# UNDP_Shield_LoRa.net
KiCad netlist of a schematic drawn in EAGLE
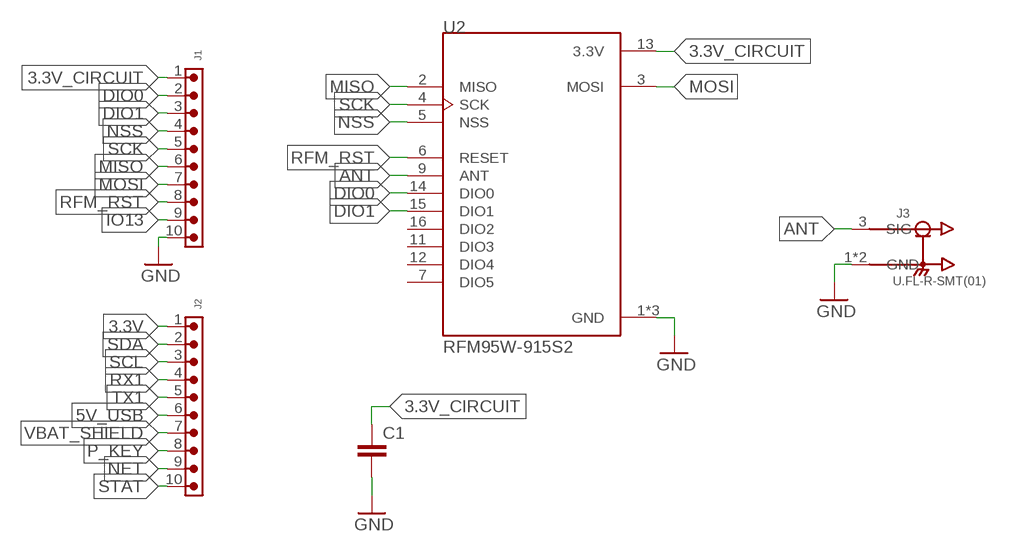
[diagram p0: schematic, sheet 1]

(export (version "E")
  (design (tool "Eeschema 10.0.6"))
  (components
    (comp (ref "C1")
      (value "C-EUC0603")
      (footprint "eagle-import:C0603")
      (libsource (lib "eagle-import") (part "C-EUC0603"))
    )
    (comp (ref "J1")
      (value "6200XX11121_62001011121")
      (footprint "eagle-import:62001011121")
      (libsource (lib "eagle-import") (part "6200XX11121_62001011121"))
    )
    (comp (ref "J2")
      (value "6200XX11121_62001011121")
      (footprint "eagle-import:62001011121")
      (libsource (lib "eagle-import") (part "6200XX11121_62001011121"))
    )
    (comp (ref "J3")
      (value "U.FL-R-SMT(01)")
      (footprint "eagle-import:HRS_U.FL-R-SMT(01)")
      (fields (field (name "MF") "Hirose"))
      (libsource (lib "eagle-import") (part "U.FL-R-SMT(01)"))
    )
    (comp (ref "U2")
      (value "RFM95W-915S2")
      (footprint "eagle-import:XCVR_RFM95W-915S2")
      (fields (field (name "MF") "RF Solutions"))
      (libsource (lib "eagle-import") (part "RFM95W-915S2"))
    )
  )
  (nets
    (net (code "1") (name "3.3V") (class "Default")
      (node (ref "J2") (pin "1") (pinfunction "1_1") (pintype "passive"))
    )
    (net (code "2") (name "3.3V_CIRCUIT") (class "Default")
      (node (ref "C1") (pin "1") (pinfunction "1_1") (pintype "passive"))
      (node (ref "J1") (pin "1") (pinfunction "1_1") (pintype "passive"))
      (node (ref "U2") (pin "13") (pinfunction "3.3V_13") (pintype "power_in"))
    )
    (net (code "3") (name "5V_USB") (class "Default")
      (node (ref "J2") (pin "6") (pinfunction "6_6") (pintype "passive"))
    )
    (net (code "4") (name "ANT") (class "Default")
      (node (ref "J3") (pin "3") (pinfunction "SIG_3") (pintype "passive"))
      (node (ref "U2") (pin "9") (pinfunction "ANT_9") (pintype "bidirectional"))
    )
    (net (code "5") (name "DIO0") (class "Default")
      (node (ref "J1") (pin "2") (pinfunction "2_2") (pintype "passive"))
      (node (ref "U2") (pin "14") (pinfunction "DIO0_14") (pintype "bidirectional"))
    )
    (net (code "6") (name "DIO1") (class "Default")
      (node (ref "J1") (pin "3") (pinfunction "3_3") (pintype "passive"))
      (node (ref "U2") (pin "15") (pinfunction "DIO1_15") (pintype "bidirectional"))
    )
    (net (code "7") (name "GND") (class "Default")
      (node (ref "C1") (pin "2") (pinfunction "2_2") (pintype "passive"))
      (node (ref "J1") (pin "10") (pinfunction "10_10") (pintype "passive"))
      (node (ref "J3") (pin "1") (pinfunction "GND_1") (pintype "passive"))
      (node (ref "J3") (pin "2") (pinfunction "GND_2") (pintype "passive"))
      (node (ref "U2") (pin "1") (pinfunction "GND_1") (pintype "power_in"))
      (node (ref "U2") (pin "10") (pinfunction "GND_10") (pintype "power_in"))
      (node (ref "U2") (pin "8") (pinfunction "GND_8") (pintype "power_in"))
    )
    (net (code "8") (name "IO13") (class "Default")
      (node (ref "J1") (pin "9") (pinfunction "9_9") (pintype "passive"))
    )
    (net (code "9") (name "MISO") (class "Default")
      (node (ref "J1") (pin "6") (pinfunction "6_6") (pintype "passive"))
      (node (ref "U2") (pin "2") (pinfunction "MISO_2") (pintype "input"))
    )
    (net (code "10") (name "MOSI") (class "Default")
      (node (ref "J1") (pin "7") (pinfunction "7_7") (pintype "passive"))
      (node (ref "U2") (pin "3") (pinfunction "MOSI_3") (pintype "output"))
    )
    (net (code "11") (name "NET") (class "Default")
      (node (ref "J2") (pin "9") (pinfunction "9_9") (pintype "passive"))
    )
    (net (code "12") (name "NSS") (class "Default")
      (node (ref "J1") (pin "4") (pinfunction "4_4") (pintype "passive"))
      (node (ref "U2") (pin "5") (pinfunction "NSS_5") (pintype "input"))
    )
    (net (code "13") (name "P_KEY") (class "Default")
      (node (ref "J2") (pin "8") (pinfunction "8_8") (pintype "passive"))
    )
    (net (code "14") (name "RFM_RST") (class "Default")
      (node (ref "J1") (pin "8") (pinfunction "8_8") (pintype "passive"))
      (node (ref "U2") (pin "6") (pinfunction "RESET_6") (pintype "bidirectional"))
    )
    (net (code "15") (name "RX1") (class "Default")
      (node (ref "J2") (pin "4") (pinfunction "4_4") (pintype "passive"))
    )
    (net (code "16") (name "SCK") (class "Default")
      (node (ref "J1") (pin "5") (pinfunction "5_5") (pintype "passive"))
      (node (ref "U2") (pin "4") (pinfunction "SCK_4") (pintype "input"))
    )
    (net (code "17") (name "SCL") (class "Default")
      (node (ref "J2") (pin "3") (pinfunction "3_3") (pintype "passive"))
    )
    (net (code "18") (name "SDA") (class "Default")
      (node (ref "J2") (pin "2") (pinfunction "2_2") (pintype "passive"))
    )
    (net (code "19") (name "STAT") (class "Default")
      (node (ref "J2") (pin "10") (pinfunction "10_10") (pintype "passive"))
    )
    (net (code "20") (name "TX1") (class "Default")
      (node (ref "J2") (pin "5") (pinfunction "5_5") (pintype "passive"))
    )
    (net (code "21") (name "VBAT_SHIELD") (class "Default")
      (node (ref "J2") (pin "7") (pinfunction "7_7") (pintype "passive"))
    )
    (net (code "22") (name "unconnected-(U2-DIO2-Pad16)") (class "Default")
      (node (ref "U2") (pin "16") (pinfunction "DIO2_16") (pintype "bidirectional"))
    )
    (net (code "23") (name "unconnected-(U2-DIO3-Pad11)") (class "Default")
      (node (ref "U2") (pin "11") (pinfunction "DIO3_11") (pintype "bidirectional"))
    )
    (net (code "24") (name "unconnected-(U2-DIO4-Pad12)") (class "Default")
      (node (ref "U2") (pin "12") (pinfunction "DIO4_12") (pintype "bidirectional"))
    )
    (net (code "25") (name "unconnected-(U2-DIO5-Pad7)") (class "Default")
      (node (ref "U2") (pin "7") (pinfunction "DIO5_7") (pintype "bidirectional"))
    )
  )
)
